# 3_PSU.net
KiCad netlist of a schematic drawn in Altium Designer
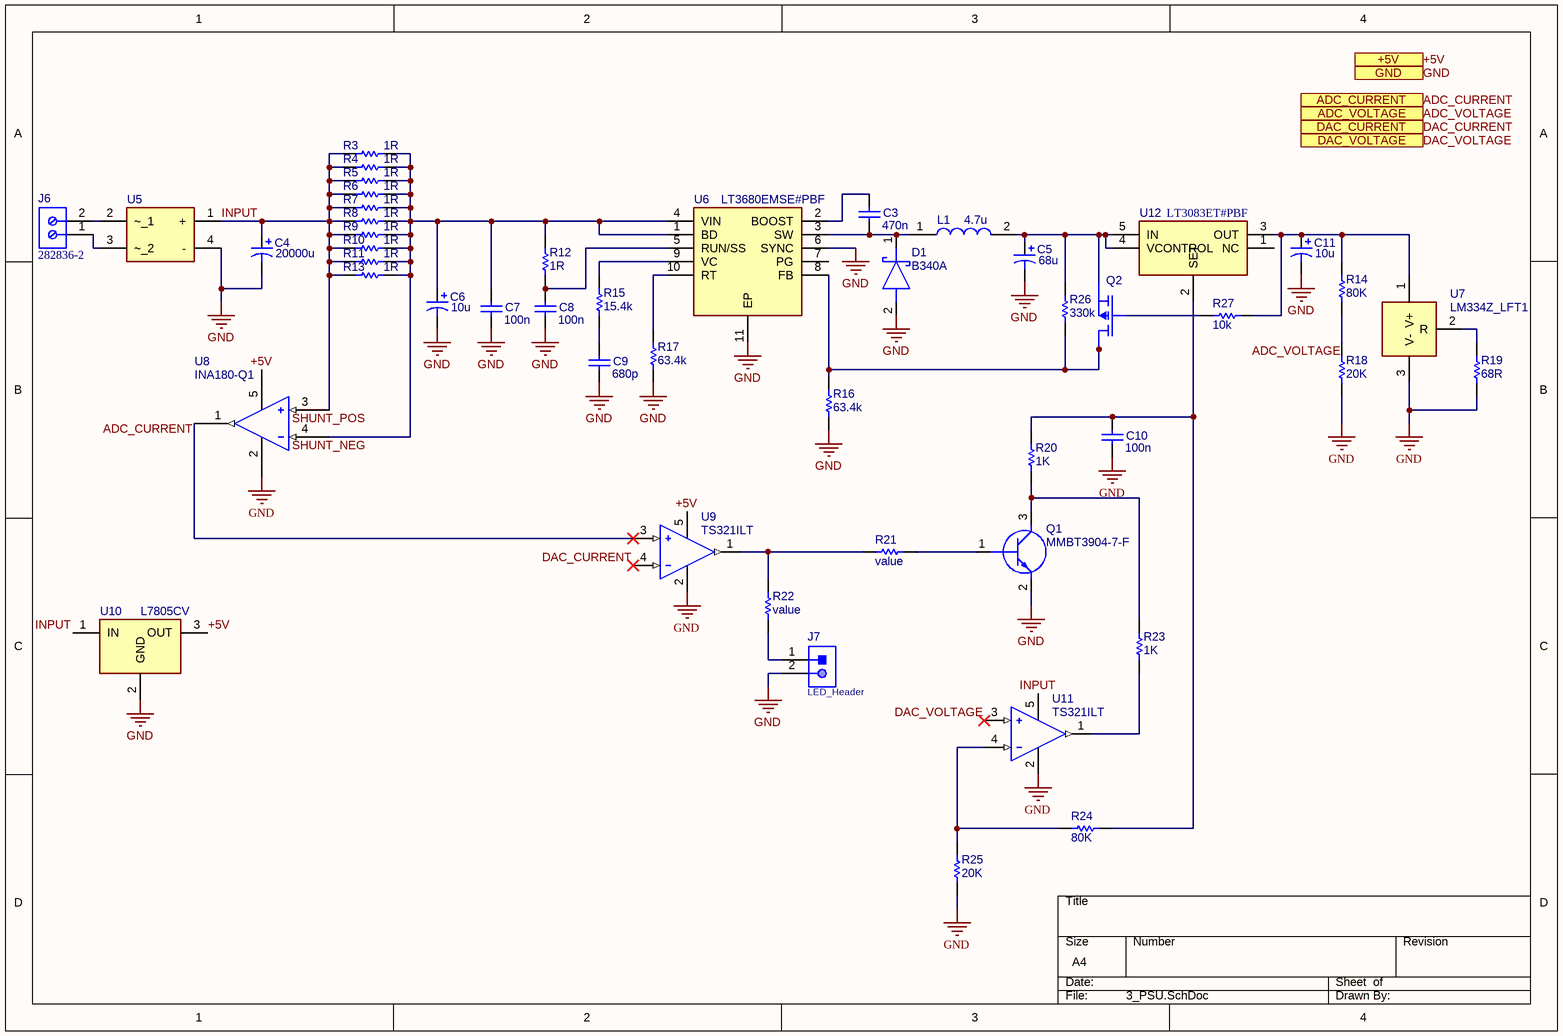
[diagram p0: 3_PSU.SchDoc]

(export (version "E")
  (design (tool "Eeschema 10.0.6"))
  (components
    (comp (ref "C3")
      (value "470n")
      (footprint "6-0805_M")
      (description "Capacitor")
      (libsource (lib "Simulation Generic Components") (part "Capacitor"))
    )
    (comp (ref "C4")
      (value "20000u")
      (description "Polarized Capacitor (Radial)")
      (fields (field (name "Comment") "Cap Pol1") (field (name "PUBLISHER") "Altium Limited"))
      (libsource (lib "Miscellaneous Devices") (part "Cap Pol1"))
    )
    (comp (ref "C5")
      (value "68u")
      (description "Polarized Capacitor (Radial)")
      (fields (field (name "Comment") "Cap Pol1") (field (name "PUBLISHER") "Altium Limited"))
      (libsource (lib "Miscellaneous Devices") (part "Cap Pol1"))
    )
    (comp (ref "C6")
      (value "10u")
      (description "Polarized Capacitor (Radial)")
      (fields (field (name "Comment") "Cap Pol1") (field (name "PUBLISHER") "Altium Limited"))
      (libsource (lib "Miscellaneous Devices") (part "Cap Pol1"))
    )
    (comp (ref "C7")
      (value "100n")
      (footprint "6-0805_M")
      (description "Capacitor")
      (libsource (lib "Simulation Generic Components") (part "Capacitor"))
    )
    (comp (ref "C8")
      (value "100n")
      (footprint "6-0805_M")
      (description "Capacitor")
      (libsource (lib "Simulation Generic Components") (part "Capacitor"))
    )
    (comp (ref "C9")
      (value "680p")
      (footprint "6-0805_M")
      (description "Capacitor")
      (libsource (lib "Simulation Generic Components") (part "Capacitor"))
    )
    (comp (ref "C10")
      (value "100n")
      (footprint "6-0805_M")
      (description "Capacitor")
      (libsource (lib "Simulation Generic Components") (part "Capacitor"))
    )
    (comp (ref "C11")
      (value "10u")
      (description "Polarized Capacitor (Radial)")
      (fields (field (name "Comment") "Cap Pol1") (field (name "PUBLISHER") "Altium Limited"))
      (libsource (lib "Miscellaneous Devices") (part "Cap Pol1"))
    )
    (comp (ref "D1")
      (value "B340A")
      (footprint "PowerSupplyPE:DIOM5127X229N")
      (description "Diode")
      (fields
        (field (name "MANUFACTURER_PART_NUMBER") "B340A-E3/61T")
        (field (name "MOUSER PART NUMBER") "625-BD340A-E3/61T")
      )
      (libsource (lib "PowerSupplyPE") (part "B340A-E3_61T"))
    )
    (comp (ref "J6")
      (value "282836-2")
      (footprint "TECO-282836-2_V")
      (description "Female Header, Pitch 5 mm, 1 x 2 Position, Height 10 mm, Tail Length 3.5 mm, Rohs, Bulk")
      (fields (field (name "VOLTAGE") "300V") (field (name "MANUFACTURER") "TE Connectivity"))
      (libsource (lib "Altium Content Vault") (part "CN-1P-F-TB2"))
    )
    (comp (ref "J7")
      (value "LED_Header")
      (footprint "61300211121")
      (description "THT Vertical Pin Header WR-PHD, Pitch 2.54 mm, Single Row, 2 pins")
      (fields
        (field (name "MANUFACTURER") "Wurth Elektronik")
        (field (name "PART NUMBER") "61300211121")
        (field (name "PUBLISHER") "WurthElektronik")
      )
      (libsource (lib "Altium Content Vault") (part "WE-CN-1P-M-R2"))
    )
    (comp (ref "L1")
      (value "4.7u")
      (footprint "PowerSupplyPE:VLS5045EX330M")
      (description "VLS5045EX-4R7M-H")
      (fields (field (name "MOUSER PART NUMBER") "810-VLS5045EX-4R7M-H"))
      (libsource (lib "PowerSupplyPE") (part "VLS5045EX-4R7M-H"))
    )
    (comp (ref "Q1")
      (value "MMBT3904-7-F")
      (footprint "SamacSys:SOT96P240X110-3N")
      (description "Transistor BJT NPN")
      (fields (field (name "MOUSER PART NUMBER") "621-MMBT3904-F"))
      (libsource (lib "*") (part "MMBT3904-7-F"))
    )
    (comp (ref "Q2")
      (value "ZVP4525GTA")
      (footprint "PowerSupplyPE:SOT230P700X180-4N")
      (description "Diodes Inc ZVP4525GTA P-channel MOSFET Transistor")
      (fields (field (name "MOUSER PART NUMBER") "522-ZVP4525GTA"))
      (libsource (lib "PowerSupplyPE") (part "ZVP4525GTA"))
    )
    (comp (ref "R3")
      (value "1R")
      (footprint "6-0805_M")
      (description "Shunt")
      (fields (field (name "Comment") "Resistor"))
      (libsource (lib "Simulation Generic Components") (part "Resistor"))
    )
    (comp (ref "R4")
      (value "1R")
      (footprint "6-0805_M")
      (description "Shunt")
      (fields (field (name "Comment") "Resistor"))
      (libsource (lib "Simulation Generic Components") (part "Resistor"))
    )
    (comp (ref "R5")
      (value "1R")
      (footprint "6-0805_M")
      (description "Shunt")
      (fields (field (name "Comment") "Resistor"))
      (libsource (lib "Simulation Generic Components") (part "Resistor"))
    )
    (comp (ref "R6")
      (value "1R")
      (footprint "6-0805_M")
      (description "Shunt")
      (fields (field (name "Comment") "Resistor"))
      (libsource (lib "Simulation Generic Components") (part "Resistor"))
    )
    (comp (ref "R7")
      (value "1R")
      (footprint "6-0805_M")
      (description "Shunt")
      (fields (field (name "Comment") "Resistor"))
      (libsource (lib "Simulation Generic Components") (part "Resistor"))
    )
    (comp (ref "R8")
      (value "1R")
      (footprint "6-0805_M")
      (description "Shunt")
      (fields (field (name "Comment") "Resistor"))
      (libsource (lib "Simulation Generic Components") (part "Resistor"))
    )
    (comp (ref "R9")
      (value "1R")
      (footprint "6-0805_M")
      (description "Shunt")
      (fields (field (name "Comment") "Resistor"))
      (libsource (lib "Simulation Generic Components") (part "Resistor"))
    )
    (comp (ref "R10")
      (value "1R")
      (footprint "6-0805_M")
      (description "Shunt")
      (fields (field (name "Comment") "Resistor"))
      (libsource (lib "Simulation Generic Components") (part "Resistor"))
    )
    (comp (ref "R11")
      (value "1R")
      (footprint "6-0805_M")
      (description "Shunt")
      (fields (field (name "Comment") "Resistor"))
      (libsource (lib "Simulation Generic Components") (part "Resistor"))
    )
    (comp (ref "R12")
      (value "1R")
      (footprint "6-0805_M")
      (description "Shunt")
      (fields (field (name "Comment") "Resistor"))
      (libsource (lib "Simulation Generic Components") (part "Resistor"))
    )
    (comp (ref "R13")
      (value "1R")
      (footprint "6-0805_M")
      (description "Shunt")
      (fields (field (name "Comment") "Resistor"))
      (libsource (lib "Simulation Generic Components") (part "Resistor"))
    )
    (comp (ref "R14")
      (value "80K")
      (footprint "6-0805_M")
      (description "Shunt")
      (fields (field (name "Comment") "Resistor"))
      (libsource (lib "Simulation Generic Components") (part "Resistor"))
    )
    (comp (ref "R15")
      (value "15.4k")
      (footprint "6-0805_M")
      (description "Shunt")
      (fields (field (name "Comment") "Resistor"))
      (libsource (lib "Simulation Generic Components") (part "Resistor"))
    )
    (comp (ref "R16")
      (value "63.4k")
      (footprint "6-0805_M")
      (description "Shunt")
      (fields (field (name "Comment") "Resistor"))
      (libsource (lib "Simulation Generic Components") (part "Resistor"))
    )
    (comp (ref "R17")
      (value "63.4k")
      (footprint "6-0805_M")
      (description "Shunt")
      (fields (field (name "Comment") "Resistor"))
      (libsource (lib "Simulation Generic Components") (part "Resistor"))
    )
    (comp (ref "R18")
      (value "20K")
      (footprint "6-0805_M")
      (description "Shunt")
      (fields (field (name "Comment") "Resistor"))
      (libsource (lib "Simulation Generic Components") (part "Resistor"))
    )
    (comp (ref "R19")
      (value "68R")
      (footprint "6-0805_M")
      (description "Shunt")
      (fields (field (name "Comment") "Resistor"))
      (libsource (lib "Simulation Generic Components") (part "Resistor"))
    )
    (comp (ref "R20")
      (value "1K")
      (footprint "6-0805_M")
      (description "Shunt")
      (fields (field (name "Comment") "Resistor"))
      (libsource (lib "Simulation Generic Components") (part "Resistor"))
    )
    (comp (ref "R21")
      (value "value")
      (footprint "6-0805_M")
      (description "Shunt")
      (fields (field (name "Comment") "Resistor"))
      (libsource (lib "Simulation Generic Components") (part "Resistor"))
    )
    (comp (ref "R22")
      (value "value")
      (footprint "6-0805_M")
      (description "Shunt")
      (fields (field (name "Comment") "Resistor"))
      (libsource (lib "Simulation Generic Components") (part "Resistor"))
    )
    (comp (ref "R23")
      (value "1K")
      (footprint "6-0805_M")
      (description "Shunt")
      (fields (field (name "Comment") "Resistor"))
      (libsource (lib "Simulation Generic Components") (part "Resistor"))
    )
    (comp (ref "R24")
      (value "80K")
      (footprint "6-0805_M")
      (description "Shunt")
      (fields (field (name "Comment") "Resistor"))
      (libsource (lib "Simulation Generic Components") (part "Resistor"))
    )
    (comp (ref "R25")
      (value "20K")
      (footprint "6-0805_M")
      (description "Shunt")
      (fields (field (name "Comment") "Resistor"))
      (libsource (lib "Simulation Generic Components") (part "Resistor"))
    )
    (comp (ref "R26")
      (value "330k")
      (footprint "6-0805_M")
      (description "Shunt")
      (fields (field (name "Comment") "Resistor"))
      (libsource (lib "Simulation Generic Components") (part "Resistor"))
    )
    (comp (ref "R27")
      (value "10k")
      (footprint "6-0805_M")
      (description "Shunt")
      (fields (field (name "Comment") "Resistor"))
      (libsource (lib "Simulation Generic Components") (part "Resistor"))
    )
    (comp (ref "U5")
      (value "GBU1010_T0_00601")
      (footprint "GBU1010_T0_00601")
      (description "Bridge Rectifier")
      (fields (field (name "MOUSER PART NUMBER") "241-GBU1010_T0_00601"))
      (libsource (lib "PowerSupplyPE") (part "GBU1010_T0_00601"))
    )
    (comp (ref "U6")
      (value "LT3680EMSE#PBF")
      (footprint "PowerSupplyPE:SOP50P490X110-11N")
      (description "Integrated Circuit")
      (fields (field (name "MOUSER PART NUMBER") "584-LT3680EMSE#PBF"))
      (libsource (lib "PowerSupplyPE") (part "LT3680EMSE#PBF"))
    )
    (comp (ref "U7")
      (value "LM334Z_LFT1")
      (footprint "LP0003A")
      (description "Integrated Circuit")
      (fields
        (field (name "MANUFACTURER_PART_NUMBER") "LM334Z/LFT1")
        (field (name "MOUSER PART NUMBER") "926-LM334Z/LFT1")
      )
      (libsource (lib "PowerSupplyPE") (part "LM334Z_LFT1"))
    )
    (comp (ref "U8")
      (value "INA180-Q1")
      (footprint "SOT95P280X145-5N")
      (description "Current Sense Amplifier")
      (libsource (lib "PowerSupplyPE") (part "INA180-Q1"))
    )
    (comp (ref "U9")
      (value "TS321ILT")
      (footprint "SOT95P280X145-5N")
      (description "Integrated Circuit")
      (fields (field (name "MOUSER PART NUMBER") "511-TS321IL"))
      (libsource (lib "PowerSupplyPE") (part "TS321ILT"))
    )
    (comp (ref "U10")
      (value "L7805CV")
      (footprint "TO255P460X1020X2008-3P")
      (description "Integrated Circuit")
      (fields (field (name "MOUSER PART NUMBER") "511-L7805CV"))
      (libsource (lib "PowerSupplyPE") (part "L7805CV"))
    )
    (comp (ref "U11")
      (value "TS321ILT")
      (footprint "SOT95P280X145-5N")
      (description "Integrated Circuit")
      (fields (field (name "MOUSER PART NUMBER") "511-TS321IL"))
      (libsource (lib "PowerSupplyPE") (part "TS321ILT"))
    )
    (comp (ref "U12")
      (value "LT3083ET#PBF")
      (footprint "SamacSys:TO170P457X1022X2306-5P")
      (description "IC REG LDO ADJ 3A TO220-5")
      (fields (field (name "MOUSER PART NUMBER") "584-LT3083ET#PBF"))
      (libsource (lib "PowerSupplyPE") (part "LT3083ET#PBF"))
    )
  )
  (nets
    (net (code "1") (name "/+5V") (class "Default")
      (node (ref "U10") (pin "3") (pinfunction "OUT_3") (pintype "power_in"))
      (node (ref "U8") (pin "5") (pinfunction "VS_5") (pintype "power_in"))
      (node (ref "U9") (pin "5") (pinfunction "VCC+_5") (pintype "power_in"))
    )
    (net (code "2") (name "/ADC_CURRENT") (class "Default")
      (node (ref "U8") (pin "1") (pinfunction "OUT_1") (pintype "output"))
      (node (ref "U9") (pin "3") (pinfunction "NON-INVERTING_INPUT_3") (pintype "input"))
    )
    (net (code "3") (name "/ADC_VOLTAGE") (class "Default")
      (node (ref "R14") (pin "1") (pinfunction "1_1") (pintype "passive"))
      (node (ref "R18") (pin "2") (pinfunction "2_2") (pintype "passive"))
    )
    (net (code "4") (name "/DAC_CURRENT") (class "Default")
      (node (ref "U9") (pin "4") (pinfunction "INVERTING_INPUT_4") (pintype "input+no_connect"))
    )
    (net (code "5") (name "/DAC_VOLTAGE") (class "Default")
      (node (ref "U11") (pin "3") (pinfunction "NON-INVERTING_INPUT_3") (pintype "input"))
    )
    (net (code "6") (name "/INPUT") (class "Default")
      (node (ref "C4") (pin "1") (pinfunction "1_1") (pintype "passive"))
      (node (ref "R10") (pin "1") (pinfunction "1_1") (pintype "passive"))
      (node (ref "R11") (pin "1") (pinfunction "1_1") (pintype "passive"))
      (node (ref "R13") (pin "1") (pinfunction "1_1") (pintype "passive"))
      (node (ref "R3") (pin "1") (pinfunction "1_1") (pintype "passive"))
      (node (ref "R4") (pin "1") (pinfunction "1_1") (pintype "passive"))
      (node (ref "R5") (pin "1") (pinfunction "1_1") (pintype "passive"))
      (node (ref "R6") (pin "1") (pinfunction "1_1") (pintype "passive"))
      (node (ref "R7") (pin "1") (pinfunction "1_1") (pintype "passive"))
      (node (ref "R8") (pin "1") (pinfunction "1_1") (pintype "passive"))
      (node (ref "R9") (pin "1") (pinfunction "1_1") (pintype "passive"))
      (node (ref "U10") (pin "1") (pinfunction "IN_1") (pintype "power_in"))
      (node (ref "U11") (pin "5") (pinfunction "VCC+_5") (pintype "power_in"))
      (node (ref "U5") (pin "1") (pinfunction "+_1") (pintype "passive"))
      (node (ref "U8") (pin "3") (pinfunction "IN+_3") (pintype "input"))
    )
    (net (code "7") (name "/SHUNT_NEG") (class "Default")
      (node (ref "C6") (pin "1") (pinfunction "1_1") (pintype "passive"))
      (node (ref "C7") (pin "2") (pinfunction "2_2") (pintype "passive"))
      (node (ref "R10") (pin "2") (pinfunction "2_2") (pintype "passive"))
      (node (ref "R11") (pin "2") (pinfunction "2_2") (pintype "passive"))
      (node (ref "R12") (pin "2") (pinfunction "2_2") (pintype "passive"))
      (node (ref "R13") (pin "2") (pinfunction "2_2") (pintype "passive"))
      (node (ref "R3") (pin "2") (pinfunction "2_2") (pintype "passive"))
      (node (ref "R4") (pin "2") (pinfunction "2_2") (pintype "passive"))
      (node (ref "R5") (pin "2") (pinfunction "2_2") (pintype "passive"))
      (node (ref "R6") (pin "2") (pinfunction "2_2") (pintype "passive"))
      (node (ref "R7") (pin "2") (pinfunction "2_2") (pintype "passive"))
      (node (ref "R8") (pin "2") (pinfunction "2_2") (pintype "passive"))
      (node (ref "R9") (pin "2") (pinfunction "2_2") (pintype "passive"))
      (node (ref "U6") (pin "1") (pinfunction "BD_1") (pintype "passive"))
      (node (ref "U6") (pin "4") (pinfunction "VIN_4") (pintype "passive"))
      (node (ref "U8") (pin "4") (pinfunction "IN-_4") (pintype "input"))
    )
    (net (code "8") (name "GND") (class "Default")
      (node (ref "C10") (pin "1") (pinfunction "1_1") (pintype "passive"))
      (node (ref "C11") (pin "2") (pinfunction "2_2") (pintype "passive"))
      (node (ref "C4") (pin "2") (pinfunction "2_2") (pintype "passive"))
      (node (ref "C5") (pin "2") (pinfunction "2_2") (pintype "passive"))
      (node (ref "C6") (pin "2") (pinfunction "2_2") (pintype "passive"))
      (node (ref "C7") (pin "1") (pinfunction "1_1") (pintype "passive"))
      (node (ref "C8") (pin "1") (pinfunction "1_1") (pintype "passive"))
      (node (ref "C9") (pin "1") (pinfunction "1_1") (pintype "passive"))
      (node (ref "D1") (pin "2") (pinfunction "A_2") (pintype "passive"))
      (node (ref "J7") (pin "2") (pinfunction "2_2") (pintype "passive"))
      (node (ref "Q1") (pin "2") (pinfunction "E_2") (pintype "passive"))
      (node (ref "R16") (pin "1") (pinfunction "1_1") (pintype "passive"))
      (node (ref "R17") (pin "1") (pinfunction "1_1") (pintype "passive"))
      (node (ref "R18") (pin "1") (pinfunction "1_1") (pintype "passive"))
      (node (ref "R19") (pin "1") (pinfunction "1_1") (pintype "passive"))
      (node (ref "R25") (pin "1") (pinfunction "1_1") (pintype "passive"))
      (node (ref "U10") (pin "2") (pinfunction "GND_2") (pintype "power_in"))
      (node (ref "U11") (pin "2") (pinfunction "VCC-_2") (pintype "power_in"))
      (node (ref "U5") (pin "4") (pinfunction "-_4") (pintype "passive"))
      (node (ref "U6") (pin "11") (pinfunction "EP_11") (pintype "passive"))
      (node (ref "U6") (pin "6") (pinfunction "SYNC_6") (pintype "passive"))
      (node (ref "U7") (pin "3") (pinfunction "V-_3") (pintype "passive"))
      (node (ref "U8") (pin "2") (pinfunction "GND_2") (pintype "power_in"))
      (node (ref "U9") (pin "2") (pinfunction "VCC-_2") (pintype "power_in"))
    )
    (net (code "9") (name "Net-(C9-Pad2)") (class "Default")
      (node (ref "C9") (pin "2") (pinfunction "2_2") (pintype "passive"))
      (node (ref "R15") (pin "1") (pinfunction "1_1") (pintype "passive"))
    )
    (net (code "10") (name "Net-(D1-K)") (class "Default")
      (node (ref "C3") (pin "1") (pinfunction "1_1") (pintype "passive"))
      (node (ref "D1") (pin "1") (pinfunction "K_1") (pintype "passive"))
      (node (ref "L1") (pin "1") (pinfunction "1_1") (pintype "passive"))
      (node (ref "U6") (pin "3") (pinfunction "SW_3") (pintype "passive"))
    )
    (net (code "11") (name "Net-(J7-Pad1)") (class "Default")
      (node (ref "J7") (pin "1") (pinfunction "1_1") (pintype "passive"))
      (node (ref "R22") (pin "1") (pinfunction "1_1") (pintype "passive"))
    )
    (net (code "12") (name "Net-(Q1-B)") (class "Default")
      (node (ref "Q1") (pin "1") (pinfunction "B_1") (pintype "passive"))
      (node (ref "R21") (pin "2") (pinfunction "2_2") (pintype "passive"))
    )
    (net (code "13") (name "Net-(Q1-C)") (class "Default")
      (node (ref "Q1") (pin "3") (pinfunction "C_3") (pintype "passive"))
      (node (ref "R20") (pin "1") (pinfunction "1_1") (pintype "passive"))
      (node (ref "R23") (pin "2") (pinfunction "2_2") (pintype "passive"))
    )
    (net (code "14") (name "Net-(Q2-D_1)") (class "Default")
      (node (ref "Q2") (pin "2") (pinfunction "D_1_2") (pintype "passive"))
      (node (ref "Q2") (pin "4") (pinfunction "D_2_4") (pintype "passive"))
      (node (ref "R16") (pin "2") (pinfunction "2_2") (pintype "passive"))
      (node (ref "R26") (pin "1") (pinfunction "1_1") (pintype "passive"))
      (node (ref "U6") (pin "8") (pinfunction "FB_8") (pintype "passive"))
    )
    (net (code "15") (name "Net-(Q2-G)") (class "Default")
      (node (ref "Q2") (pin "1") (pinfunction "G_1") (pintype "passive"))
      (node (ref "R27") (pin "2") (pinfunction "2_2") (pintype "passive"))
    )
    (net (code "16") (name "Net-(Q2-S)") (class "Default")
      (node (ref "C5") (pin "1") (pinfunction "1_1") (pintype "passive"))
      (node (ref "L1") (pin "2") (pinfunction "2_2") (pintype "passive"))
      (node (ref "Q2") (pin "3") (pinfunction "S_3") (pintype "passive"))
      (node (ref "R26") (pin "2") (pinfunction "2_2") (pintype "passive"))
      (node (ref "U12") (pin "4") (pinfunction "VCONTROL_4") (pintype "passive"))
      (node (ref "U12") (pin "5") (pinfunction "IN_5") (pintype "passive"))
    )
    (net (code "17") (name "Net-(U5-~_1)") (class "Default")
      (node (ref "J6") (pin "2") (pinfunction "2_2") (pintype "passive"))
      (node (ref "U5") (pin "2") (pinfunction "~_1_2") (pintype "passive"))
    )
    (net (code "18") (name "Net-(U5-~_2)") (class "Default")
      (node (ref "J6") (pin "1") (pinfunction "1_1") (pintype "passive"))
      (node (ref "U5") (pin "3") (pinfunction "~_2_3") (pintype "passive"))
    )
    (net (code "19") (name "Net-(U6-BOOST)") (class "Default")
      (node (ref "C3") (pin "2") (pinfunction "2_2") (pintype "passive"))
      (node (ref "U6") (pin "2") (pinfunction "BOOST_2") (pintype "passive"))
    )
    (net (code "20") (name "Net-(U6-RT)") (class "Default")
      (node (ref "R17") (pin "2") (pinfunction "2_2") (pintype "passive"))
      (node (ref "U6") (pin "10") (pinfunction "RT_10") (pintype "passive"))
    )
    (net (code "21") (name "Net-(U6-RUN{slash}SS)") (class "Default")
      (node (ref "C8") (pin "2") (pinfunction "2_2") (pintype "passive"))
      (node (ref "R12") (pin "1") (pinfunction "1_1") (pintype "passive"))
      (node (ref "U6") (pin "5") (pinfunction "RUN/SS_5") (pintype "passive"))
    )
    (net (code "22") (name "Net-(U6-VC)") (class "Default")
      (node (ref "R15") (pin "2") (pinfunction "2_2") (pintype "passive"))
      (node (ref "U6") (pin "9") (pinfunction "VC_9") (pintype "passive"))
    )
    (net (code "23") (name "Net-(U7-R)") (class "Default")
      (node (ref "R19") (pin "2") (pinfunction "2_2") (pintype "passive"))
      (node (ref "U7") (pin "2") (pinfunction "R_2") (pintype "passive"))
    )
    (net (code "24") (name "Net-(U9-OUTPUT)") (class "Default")
      (node (ref "R21") (pin "1") (pinfunction "1_1") (pintype "passive"))
      (node (ref "R22") (pin "2") (pinfunction "2_2") (pintype "passive"))
      (node (ref "U9") (pin "1") (pinfunction "OUTPUT_1") (pintype "output"))
    )
    (net (code "25") (name "Net-(U11-INVERTING_INPUT)") (class "Default")
      (node (ref "R24") (pin "2") (pinfunction "2_2") (pintype "passive"))
      (node (ref "R25") (pin "2") (pinfunction "2_2") (pintype "passive"))
      (node (ref "U11") (pin "4") (pinfunction "INVERTING_INPUT_4") (pintype "input"))
    )
    (net (code "26") (name "Net-(U11-OUTPUT)") (class "Default")
      (node (ref "R23") (pin "1") (pinfunction "1_1") (pintype "passive"))
      (node (ref "U11") (pin "1") (pinfunction "OUTPUT_1") (pintype "output"))
    )
    (net (code "27") (name "Net-(U12-OUT)") (class "Default")
      (node (ref "C11") (pin "1") (pinfunction "1_1") (pintype "passive"))
      (node (ref "R14") (pin "2") (pinfunction "2_2") (pintype "passive"))
      (node (ref "R27") (pin "1") (pinfunction "1_1") (pintype "passive"))
      (node (ref "U12") (pin "3") (pinfunction "OUT_3") (pintype "passive"))
      (node (ref "U7") (pin "1") (pinfunction "V+_1") (pintype "passive"))
    )
    (net (code "28") (name "Net-(U12-SET)") (class "Default")
      (node (ref "C10") (pin "2") (pinfunction "2_2") (pintype "passive"))
      (node (ref "R20") (pin "2") (pinfunction "2_2") (pintype "passive"))
      (node (ref "R24") (pin "1") (pinfunction "1_1") (pintype "passive"))
      (node (ref "U12") (pin "2") (pinfunction "SET_2") (pintype "passive"))
    )
    (net (code "29") (name "unconnected-(U6-PG-Pad7)") (class "Default")
      (node (ref "U6") (pin "7") (pinfunction "PG_7") (pintype "passive"))
    )
    (net (code "30") (name "unconnected-(U12-NC-Pad1)") (class "Default")
      (node (ref "U12") (pin "1") (pinfunction "NC_1") (pintype "passive"))
    )
  )
)
